# SCH_SIM.net
KiCad netlist of a schematic drawn in Altium Designer
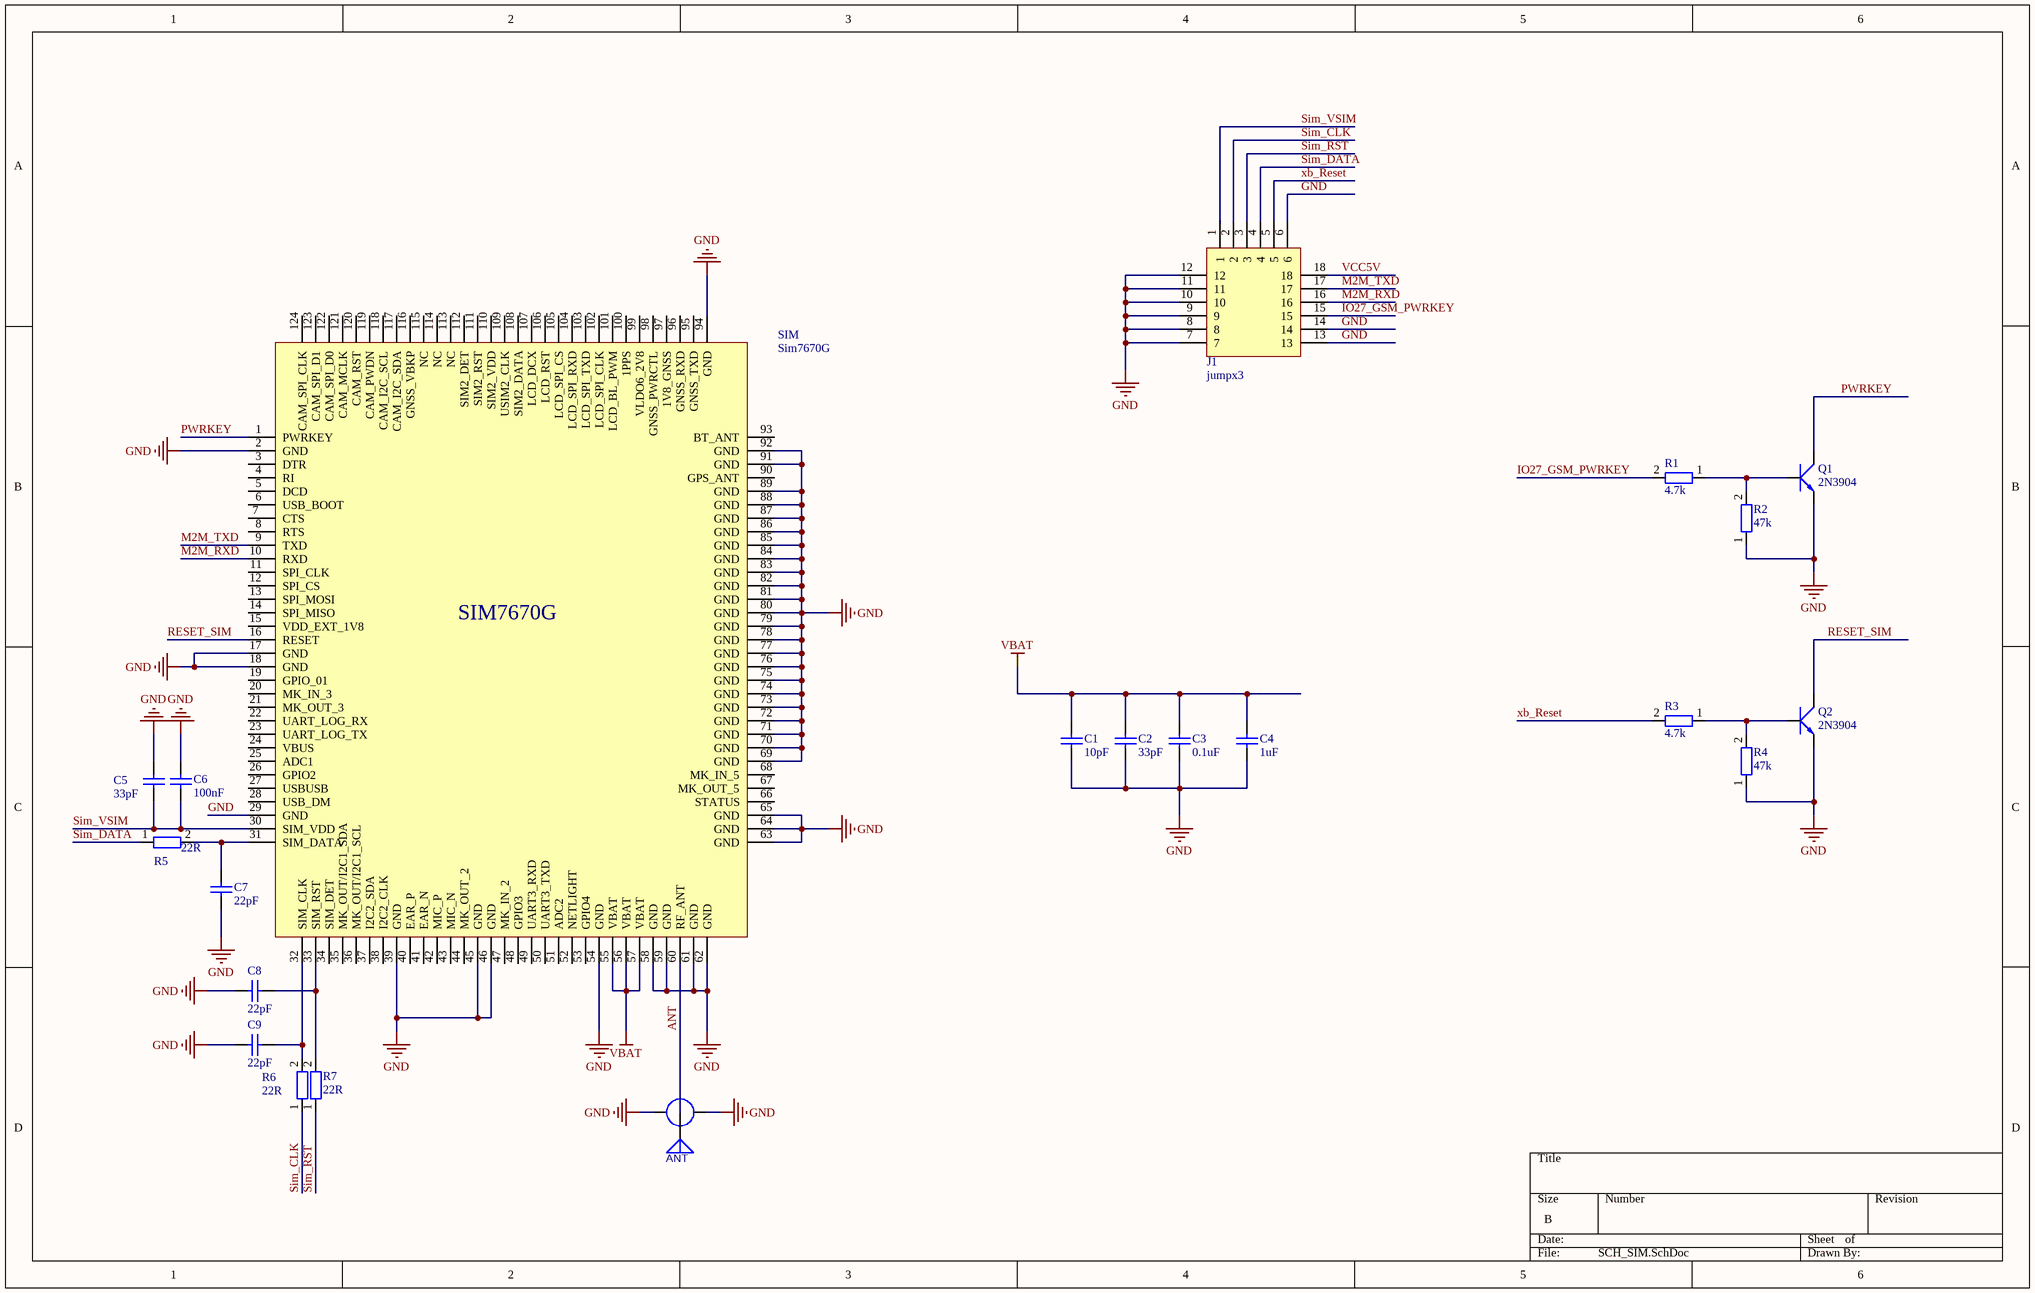
[diagram p0: SCH_SIM.SchDoc]

(export (version "E")
  (design (tool "Eeschema 10.0.6"))
  (components
    (comp (ref "ANT")
      (value "ANT")
      (footprint "CONNECTORS RF SMD TYPE IPEX")
      (description "SMD RF Connectors / Coaxial Connectors ROHS")
      (fields
        (field (name "BOM_SUPPLIER PART") "C3151745")
        (field (name "BOM_MANUFACTURER PART") "IPEX1-TXZ 142")
        (field (name "CONTRIBUTOR") "lcsc")
      )
      (libsource (lib "SCH_Library") (part "CONNECTORS RF SMD"))
    )
    (comp (ref "C1")
      (value "10pF")
      (footprint "C0201")
      (description "Capacitor")
      (libsource (lib "SCH_Library") (part "CAP104-100nF-50V"))
    )
    (comp (ref "C2")
      (value "33pF")
      (footprint "C0201")
      (description "Capacitor")
      (libsource (lib "SCH_Library") (part "CAP104-100nF-50V"))
    )
    (comp (ref "C3")
      (value "0.1uF")
      (footprint "C0201")
      (description "Capacitor")
      (libsource (lib "SCH_Library") (part "CAP104-100nF-50V"))
    )
    (comp (ref "C4")
      (value "1uF")
      (footprint "C0201")
      (description "Capacitor")
      (libsource (lib "SCH_Library") (part "CAP104-100nF-50V"))
    )
    (comp (ref "C5")
      (value "33pF")
      (footprint "C0201")
      (description "Capacitor")
      (libsource (lib "SCH_Library") (part "CAP104-100nF-50V"))
    )
    (comp (ref "C6")
      (value "100nF")
      (footprint "C0201")
      (description "Capacitor")
      (libsource (lib "SCH_Library") (part "CAP104-100nF-50V"))
    )
    (comp (ref "C7")
      (value "22pF")
      (footprint "CAP_0805")
      (description "Capacitor")
      (libsource (lib "SCH_Library") (part "CAP104-100nF-50V"))
    )
    (comp (ref "C8")
      (value "22pF")
      (footprint "C0201")
      (description "Capacitor")
      (libsource (lib "SCH_Library") (part "CAP104-100nF-50V"))
    )
    (comp (ref "C9")
      (value "22pF")
      (footprint "C0201")
      (description "Capacitor")
      (libsource (lib "SCH_Library") (part "CAP104-100nF-50V"))
    )
    (comp (ref "J1") (value "jumpx3") (libsource (lib "SCH_Library") (part "jumpx3")))
    (comp (ref "Q1")
      (value "2N3904")
      (footprint "SOT-23")
      (description "SOT-23 - C8658")
      (libsource (lib "Altium_Lib") (part "Trans BC817"))
    )
    (comp (ref "Q2")
      (value "2N3904")
      (footprint "SOT-23")
      (description "SOT-23 - C8658")
      (libsource (lib "Altium_Lib") (part "Trans BC817"))
    )
    (comp (ref "R1")
      (value "4.7k")
      (footprint "R0201")
      (description "±1% - Chip Resistor - Surface Mount ROHS")
      (libsource (lib "SCH_Library") (part "RES 0603 1%_"))
    )
    (comp (ref "R2")
      (value "47k")
      (footprint "R0201")
      (description "±1% - Chip Resistor - Surface Mount ROHS")
      (libsource (lib "SCH_Library") (part "RES 0603 1%_"))
    )
    (comp (ref "R3")
      (value "4.7k")
      (footprint "R0201")
      (description "±1% - Chip Resistor - Surface Mount ROHS")
      (libsource (lib "SCH_Library") (part "RES 0603 1%_"))
    )
    (comp (ref "R4")
      (value "47k")
      (footprint "R0201")
      (description "±1% - Chip Resistor - Surface Mount ROHS")
      (libsource (lib "SCH_Library") (part "RES 0603 1%_"))
    )
    (comp (ref "R5")
      (value "22R")
      (footprint "R0201")
      (description "±1% - Chip Resistor - Surface Mount ROHS")
      (libsource (lib "SCH_Library") (part "RES 0603 1%_"))
    )
    (comp (ref "R6")
      (value "22R")
      (footprint "R0201")
      (description "±1% - Chip Resistor - Surface Mount ROHS")
      (libsource (lib "SCH_Library") (part "RES 0603 1%_"))
    )
    (comp (ref "R7")
      (value "22R")
      (footprint "R0201")
      (description "±1% - Chip Resistor - Surface Mount ROHS")
      (libsource (lib "SCH_Library") (part "RES 0603 1%_"))
    )
    (comp (ref "SIM")
      (value "Sim7670G")
      (footprint "PCBComponent_1")
      (libsource (lib "SCH_Library") (part "Sim7670G"))
    )
  )
  (nets
    (net (code "1") (name "/ANT") (class "Default")
      (node (ref "ANT") (pin "1") (pinfunction "1_1") (pintype "passive"))
      (node (ref "SIM") (pin "60") (pinfunction "RF_ANT_60") (pintype "passive"))
    )
    (net (code "2") (name "/IO27_GSM_PWRKEY") (class "Default")
      (node (ref "J1") (pin "15") (pinfunction "15_15") (pintype "passive"))
      (node (ref "R1") (pin "2") (pinfunction "2_2") (pintype "passive"))
    )
    (net (code "3") (name "/M2M_RXD") (class "Default")
      (node (ref "J1") (pin "16") (pinfunction "16_16") (pintype "passive"))
      (node (ref "SIM") (pin "10") (pinfunction "RXD_10") (pintype "passive"))
    )
    (net (code "4") (name "/M2M_TXD") (class "Default")
      (node (ref "J1") (pin "17") (pinfunction "17_17") (pintype "passive"))
      (node (ref "SIM") (pin "9") (pinfunction "TXD_9") (pintype "passive"))
    )
    (net (code "5") (name "/PWRKEY") (class "Default")
      (node (ref "Q1") (pin "3") (pinfunction "C_3") (pintype "passive"))
      (node (ref "SIM") (pin "1") (pinfunction "PWRKEY_1") (pintype "passive"))
    )
    (net (code "6") (name "/RESET_SIM") (class "Default")
      (node (ref "Q2") (pin "3") (pinfunction "C_3") (pintype "passive"))
      (node (ref "SIM") (pin "16") (pinfunction "RESET_16") (pintype "passive"))
    )
    (net (code "7") (name "/Sim_CLK") (class "Default")
      (node (ref "J1") (pin "2") (pinfunction "2_2") (pintype "passive"))
      (node (ref "R6") (pin "1") (pinfunction "1_1") (pintype "passive"))
    )
    (net (code "8") (name "/Sim_DATA") (class "Default")
      (node (ref "J1") (pin "4") (pinfunction "4_4") (pintype "passive"))
      (node (ref "R5") (pin "1") (pinfunction "1_1") (pintype "passive"))
    )
    (net (code "9") (name "/Sim_RST") (class "Default")
      (node (ref "J1") (pin "3") (pinfunction "3_3") (pintype "passive"))
      (node (ref "R7") (pin "1") (pinfunction "1_1") (pintype "passive"))
    )
    (net (code "10") (name "/Sim_VSIM") (class "Default")
      (node (ref "C5") (pin "2") (pinfunction "2_2") (pintype "passive"))
      (node (ref "C6") (pin "2") (pinfunction "2_2") (pintype "passive"))
      (node (ref "J1") (pin "1") (pinfunction "1_1") (pintype "passive"))
      (node (ref "SIM") (pin "30") (pinfunction "SIM_VDD_30") (pintype "passive"))
    )
    (net (code "11") (name "/VCC5V") (class "Default")
      (node (ref "J1") (pin "18") (pinfunction "18_18") (pintype "passive"))
    )
    (net (code "12") (name "/xb_Reset") (class "Default")
      (node (ref "J1") (pin "5") (pinfunction "5_5") (pintype "passive"))
      (node (ref "R3") (pin "2") (pinfunction "2_2") (pintype "passive"))
    )
    (net (code "13") (name "GND") (class "Default")
      (node (ref "ANT") (pin "2") (pinfunction "2_2") (pintype "passive"))
      (node (ref "ANT") (pin "3") (pinfunction "3_3") (pintype "passive"))
      (node (ref "C1") (pin "1") (pinfunction "1_1") (pintype "passive"))
      (node (ref "C2") (pin "1") (pinfunction "1_1") (pintype "passive"))
      (node (ref "C3") (pin "1") (pinfunction "1_1") (pintype "passive"))
      (node (ref "C4") (pin "1") (pinfunction "1_1") (pintype "passive"))
      (node (ref "C5") (pin "1") (pinfunction "1_1") (pintype "passive"))
      (node (ref "C6") (pin "1") (pinfunction "1_1") (pintype "passive"))
      (node (ref "C7") (pin "2") (pinfunction "2_2") (pintype "passive"))
      (node (ref "C8") (pin "2") (pinfunction "2_2") (pintype "passive"))
      (node (ref "C9") (pin "2") (pinfunction "2_2") (pintype "passive"))
      (node (ref "J1") (pin "10") (pinfunction "10_10") (pintype "passive"))
      (node (ref "J1") (pin "11") (pinfunction "11_11") (pintype "passive"))
      (node (ref "J1") (pin "12") (pinfunction "12_12") (pintype "passive"))
      (node (ref "J1") (pin "13") (pinfunction "13_13") (pintype "passive"))
      (node (ref "J1") (pin "14") (pinfunction "14_14") (pintype "passive"))
      (node (ref "J1") (pin "6") (pinfunction "6_6") (pintype "passive"))
      (node (ref "J1") (pin "7") (pinfunction "7_7") (pintype "passive"))
      (node (ref "J1") (pin "8") (pinfunction "8_8") (pintype "passive"))
      (node (ref "J1") (pin "9") (pinfunction "9_9") (pintype "passive"))
      (node (ref "Q1") (pin "2") (pinfunction "E_2") (pintype "passive"))
      (node (ref "Q2") (pin "2") (pinfunction "E_2") (pintype "passive"))
      (node (ref "R2") (pin "1") (pinfunction "1_1") (pintype "passive"))
      (node (ref "R4") (pin "1") (pinfunction "1_1") (pintype "passive"))
      (node (ref "SIM") (pin "17") (pinfunction "GND_17") (pintype "passive"))
      (node (ref "SIM") (pin "18") (pinfunction "GND_18") (pintype "passive"))
      (node (ref "SIM") (pin "2") (pinfunction "GND_2") (pintype "passive"))
      (node (ref "SIM") (pin "29") (pinfunction "GND_29") (pintype "passive"))
      (node (ref "SIM") (pin "39") (pinfunction "GND_39") (pintype "passive"))
      (node (ref "SIM") (pin "45") (pinfunction "GND_45") (pintype "passive"))
      (node (ref "SIM") (pin "46") (pinfunction "GND_46") (pintype "passive"))
      (node (ref "SIM") (pin "54") (pinfunction "GND_54") (pintype "passive"))
      (node (ref "SIM") (pin "58") (pinfunction "GND_58") (pintype "passive"))
      (node (ref "SIM") (pin "59") (pinfunction "GND_59") (pintype "passive"))
      (node (ref "SIM") (pin "61") (pinfunction "GND_61") (pintype "passive"))
      (node (ref "SIM") (pin "62") (pinfunction "GND_62") (pintype "passive"))
      (node (ref "SIM") (pin "63") (pinfunction "GND_63") (pintype "passive"))
      (node (ref "SIM") (pin "64") (pinfunction "GND_64") (pintype "passive"))
      (node (ref "SIM") (pin "65") (pinfunction "GND_65") (pintype "passive"))
      (node (ref "SIM") (pin "69") (pinfunction "GND_69") (pintype "passive"))
      (node (ref "SIM") (pin "70") (pinfunction "GND_70") (pintype "passive"))
      (node (ref "SIM") (pin "71") (pinfunction "GND_71") (pintype "passive"))
      (node (ref "SIM") (pin "72") (pinfunction "GND_72") (pintype "passive"))
      (node (ref "SIM") (pin "73") (pinfunction "GND_73") (pintype "passive"))
      (node (ref "SIM") (pin "74") (pinfunction "GND_74") (pintype "passive"))
      (node (ref "SIM") (pin "75") (pinfunction "GND_75") (pintype "passive"))
      (node (ref "SIM") (pin "76") (pinfunction "GND_76") (pintype "passive"))
      (node (ref "SIM") (pin "77") (pinfunction "GND_77") (pintype "passive"))
      (node (ref "SIM") (pin "78") (pinfunction "GND_78") (pintype "passive"))
      (node (ref "SIM") (pin "79") (pinfunction "GND_79") (pintype "passive"))
      (node (ref "SIM") (pin "80") (pinfunction "GND_80") (pintype "passive"))
      (node (ref "SIM") (pin "81") (pinfunction "GND_81") (pintype "passive"))
      (node (ref "SIM") (pin "82") (pinfunction "GND_82") (pintype "passive"))
      (node (ref "SIM") (pin "83") (pinfunction "GND_83") (pintype "passive"))
      (node (ref "SIM") (pin "84") (pinfunction "GND_84") (pintype "passive"))
      (node (ref "SIM") (pin "85") (pinfunction "GND_85") (pintype "passive"))
      (node (ref "SIM") (pin "86") (pinfunction "GND_86") (pintype "passive"))
      (node (ref "SIM") (pin "87") (pinfunction "GND_87") (pintype "passive"))
      (node (ref "SIM") (pin "88") (pinfunction "GND_88") (pintype "passive"))
      (node (ref "SIM") (pin "89") (pinfunction "GND_89") (pintype "passive"))
      (node (ref "SIM") (pin "91") (pinfunction "GND_91") (pintype "passive"))
      (node (ref "SIM") (pin "92") (pinfunction "GND_92") (pintype "passive"))
      (node (ref "SIM") (pin "94") (pinfunction "GND_94") (pintype "passive"))
    )
    (net (code "14") (name "Net-(Q1-B)") (class "Default")
      (node (ref "Q1") (pin "1") (pinfunction "B_1") (pintype "passive"))
      (node (ref "R1") (pin "1") (pinfunction "1_1") (pintype "passive"))
      (node (ref "R2") (pin "2") (pinfunction "2_2") (pintype "passive"))
    )
    (net (code "15") (name "Net-(Q2-B)") (class "Default")
      (node (ref "Q2") (pin "1") (pinfunction "B_1") (pintype "passive"))
      (node (ref "R3") (pin "1") (pinfunction "1_1") (pintype "passive"))
      (node (ref "R4") (pin "2") (pinfunction "2_2") (pintype "passive"))
    )
    (net (code "16") (name "Net-(SIM-SIM_CLK)") (class "Default")
      (node (ref "C9") (pin "1") (pinfunction "1_1") (pintype "passive"))
      (node (ref "R6") (pin "2") (pinfunction "2_2") (pintype "passive"))
      (node (ref "SIM") (pin "32") (pinfunction "SIM_CLK_32") (pintype "passive"))
    )
    (net (code "17") (name "Net-(SIM-SIM_DATA)") (class "Default")
      (node (ref "C7") (pin "1") (pinfunction "1_1") (pintype "passive"))
      (node (ref "R5") (pin "2") (pinfunction "2_2") (pintype "passive"))
      (node (ref "SIM") (pin "31") (pinfunction "SIM_DATA_31") (pintype "passive"))
    )
    (net (code "18") (name "Net-(SIM-SIM_RST)") (class "Default")
      (node (ref "C8") (pin "1") (pinfunction "1_1") (pintype "passive"))
      (node (ref "R7") (pin "2") (pinfunction "2_2") (pintype "passive"))
      (node (ref "SIM") (pin "33") (pinfunction "SIM_RST_33") (pintype "passive"))
    )
    (net (code "19") (name "VBAT") (class "Default")
      (node (ref "C1") (pin "2") (pinfunction "2_2") (pintype "passive"))
      (node (ref "C2") (pin "2") (pinfunction "2_2") (pintype "passive"))
      (node (ref "C3") (pin "2") (pinfunction "2_2") (pintype "passive"))
      (node (ref "C4") (pin "2") (pinfunction "2_2") (pintype "passive"))
      (node (ref "SIM") (pin "55") (pinfunction "VBAT_55") (pintype "passive"))
      (node (ref "SIM") (pin "56") (pinfunction "VBAT_56") (pintype "passive"))
      (node (ref "SIM") (pin "57") (pinfunction "VBAT_57") (pintype "passive"))
    )
    (net (code "20") (name "unconnected-(SIM-1PPS-Pad100)") (class "Default")
      (node (ref "SIM") (pin "100") (pinfunction "1PPS_100") (pintype "passive"))
    )
    (net (code "21") (name "unconnected-(SIM-1V8_GNSS-Pad97)") (class "Default")
      (node (ref "SIM") (pin "97") (pinfunction "1V8_GNSS_97") (pintype "passive"))
    )
    (net (code "22") (name "unconnected-(SIM-ADC1-Pad25)") (class "Default")
      (node (ref "SIM") (pin "25") (pinfunction "ADC1_25") (pintype "passive"))
    )
    (net (code "23") (name "unconnected-(SIM-ADC2-Pad51)") (class "Default")
      (node (ref "SIM") (pin "51") (pinfunction "ADC2_51") (pintype "passive"))
    )
    (net (code "24") (name "unconnected-(SIM-BT_ANT-Pad93)") (class "Default")
      (node (ref "SIM") (pin "93") (pinfunction "BT_ANT_93") (pintype "passive"))
    )
    (net (code "25") (name "unconnected-(SIM-CAM_I2C_SCL-Pad118)") (class "Default")
      (node (ref "SIM") (pin "118") (pinfunction "CAM_I2C_SCL_118") (pintype "passive"))
    )
    (net (code "26") (name "unconnected-(SIM-CAM_I2C_SDA-Pad117)") (class "Default")
      (node (ref "SIM") (pin "117") (pinfunction "CAM_I2C_SDA_117") (pintype "passive"))
    )
    (net (code "27") (name "unconnected-(SIM-CAM_MCLK-Pad121)") (class "Default")
      (node (ref "SIM") (pin "121") (pinfunction "CAM_MCLK_121") (pintype "passive"))
    )
    (net (code "28") (name "unconnected-(SIM-CAM_PWDN-Pad119)") (class "Default")
      (node (ref "SIM") (pin "119") (pinfunction "CAM_PWDN_119") (pintype "passive"))
    )
    (net (code "29") (name "unconnected-(SIM-CAM_RST-Pad120)") (class "Default")
      (node (ref "SIM") (pin "120") (pinfunction "CAM_RST_120") (pintype "passive"))
    )
    (net (code "30") (name "unconnected-(SIM-CAM_SPI_CLK-Pad124)") (class "Default")
      (node (ref "SIM") (pin "124") (pinfunction "CAM_SPI_CLK_124") (pintype "passive"))
    )
    (net (code "31") (name "unconnected-(SIM-CAM_SPI_D0-Pad122)") (class "Default")
      (node (ref "SIM") (pin "122") (pinfunction "CAM_SPI_D0_122") (pintype "passive"))
    )
    (net (code "32") (name "unconnected-(SIM-CAM_SPI_D1-Pad123)") (class "Default")
      (node (ref "SIM") (pin "123") (pinfunction "CAM_SPI_D1_123") (pintype "passive"))
    )
    (net (code "33") (name "unconnected-(SIM-CTS-Pad7)") (class "Default")
      (node (ref "SIM") (pin "7") (pinfunction "CTS_7") (pintype "passive"))
    )
    (net (code "34") (name "unconnected-(SIM-DCD-Pad5)") (class "Default")
      (node (ref "SIM") (pin "5") (pinfunction "DCD_5") (pintype "passive"))
    )
    (net (code "35") (name "unconnected-(SIM-DTR-Pad3)") (class "Default")
      (node (ref "SIM") (pin "3") (pinfunction "DTR_3") (pintype "passive"))
    )
    (net (code "36") (name "unconnected-(SIM-EAR_N-Pad41)") (class "Default")
      (node (ref "SIM") (pin "41") (pinfunction "EAR_N_41") (pintype "passive"))
    )
    (net (code "37") (name "unconnected-(SIM-EAR_P-Pad40)") (class "Default")
      (node (ref "SIM") (pin "40") (pinfunction "EAR_P_40") (pintype "passive"))
    )
    (net (code "38") (name "unconnected-(SIM-GNSS_PWRCTL-Pad98)") (class "Default")
      (node (ref "SIM") (pin "98") (pinfunction "GNSS_PWRCTL_98") (pintype "passive"))
    )
    (net (code "39") (name "unconnected-(SIM-GNSS_RXD-Pad96)") (class "Default")
      (node (ref "SIM") (pin "96") (pinfunction "GNSS_RXD_96") (pintype "passive"))
    )
    (net (code "40") (name "unconnected-(SIM-GNSS_TXD-Pad95)") (class "Default")
      (node (ref "SIM") (pin "95") (pinfunction "GNSS_TXD_95") (pintype "passive"))
    )
    (net (code "41") (name "unconnected-(SIM-GNSS_VBKP-Pad116)") (class "Default")
      (node (ref "SIM") (pin "116") (pinfunction "GNSS_VBKP_116") (pintype "passive"))
    )
    (net (code "42") (name "unconnected-(SIM-GPIO2-Pad26)") (class "Default")
      (node (ref "SIM") (pin "26") (pinfunction "GPIO2_26") (pintype "passive"))
    )
    (net (code "43") (name "unconnected-(SIM-GPIO3-Pad48)") (class "Default")
      (node (ref "SIM") (pin "48") (pinfunction "GPIO3_48") (pintype "passive"))
    )
    (net (code "44") (name "unconnected-(SIM-GPIO4-Pad53)") (class "Default")
      (node (ref "SIM") (pin "53") (pinfunction "GPIO4_53") (pintype "passive"))
    )
    (net (code "45") (name "unconnected-(SIM-GPIO_01-Pad19)") (class "Default")
      (node (ref "SIM") (pin "19") (pinfunction "GPIO_01_19") (pintype "passive"))
    )
    (net (code "46") (name "unconnected-(SIM-GPS_ANT-Pad90)") (class "Default")
      (node (ref "SIM") (pin "90") (pinfunction "GPS_ANT_90") (pintype "passive"))
    )
    (net (code "47") (name "unconnected-(SIM-I2C2_CLK-Pad38)") (class "Default")
      (node (ref "SIM") (pin "38") (pinfunction "I2C2_CLK_38") (pintype "passive"))
    )
    (net (code "48") (name "unconnected-(SIM-I2C2_SDA-Pad37)") (class "Default")
      (node (ref "SIM") (pin "37") (pinfunction "I2C2_SDA_37") (pintype "passive"))
    )
    (net (code "49") (name "unconnected-(SIM-LCD_BL_PWM-Pad101)") (class "Default")
      (node (ref "SIM") (pin "101") (pinfunction "LCD_BL_PWM_101") (pintype "passive"))
    )
    (net (code "50") (name "unconnected-(SIM-LCD_DCX-Pad107)") (class "Default")
      (node (ref "SIM") (pin "107") (pinfunction "LCD_DCX_107") (pintype "passive"))
    )
    (net (code "51") (name "unconnected-(SIM-LCD_RST-Pad106)") (class "Default")
      (node (ref "SIM") (pin "106") (pinfunction "LCD_RST_106") (pintype "passive"))
    )
    (net (code "52") (name "unconnected-(SIM-LCD_SPI_CLK-Pad102)") (class "Default")
      (node (ref "SIM") (pin "102") (pinfunction "LCD_SPI_CLK_102") (pintype "passive"))
    )
    (net (code "53") (name "unconnected-(SIM-LCD_SPI_CS-Pad105)") (class "Default")
      (node (ref "SIM") (pin "105") (pinfunction "LCD_SPI_CS_105") (pintype "passive"))
    )
    (net (code "54") (name "unconnected-(SIM-LCD_SPI_RXD-Pad104)") (class "Default")
      (node (ref "SIM") (pin "104") (pinfunction "LCD_SPI_RXD_104") (pintype "passive"))
    )
    (net (code "55") (name "unconnected-(SIM-LCD_SPI_TXD-Pad103)") (class "Default")
      (node (ref "SIM") (pin "103") (pinfunction "LCD_SPI_TXD_103") (pintype "passive"))
    )
    (net (code "56") (name "unconnected-(SIM-MIC_N-Pad43)") (class "Default")
      (node (ref "SIM") (pin "43") (pinfunction "MIC_N_43") (pintype "passive"))
    )
    (net (code "57") (name "unconnected-(SIM-MIC_P-Pad42)") (class "Default")
      (node (ref "SIM") (pin "42") (pinfunction "MIC_P_42") (pintype "passive"))
    )
    (net (code "58") (name "unconnected-(SIM-MK_IN_2-Pad47)") (class "Default")
      (node (ref "SIM") (pin "47") (pinfunction "MK_IN_2_47") (pintype "passive"))
    )
    (net (code "59") (name "unconnected-(SIM-MK_IN_3-Pad20)") (class "Default")
      (node (ref "SIM") (pin "20") (pinfunction "MK_IN_3_20") (pintype "passive"))
    )
    (net (code "60") (name "unconnected-(SIM-MK_IN_5-Pad68)") (class "Default")
      (node (ref "SIM") (pin "68") (pinfunction "MK_IN_5_68") (pintype "passive"))
    )
    (net (code "61") (name "unconnected-(SIM-MK_OUT_2-Pad44)") (class "Default")
      (node (ref "SIM") (pin "44") (pinfunction "MK_OUT_2_44") (pintype "passive"))
    )
    (net (code "62") (name "unconnected-(SIM-MK_OUT_3-Pad21)") (class "Default")
      (node (ref "SIM") (pin "21") (pinfunction "MK_OUT_3_21") (pintype "passive"))
    )
    (net (code "63") (name "unconnected-(SIM-MK_OUT_5-Pad67)") (class "Default")
      (node (ref "SIM") (pin "67") (pinfunction "MK_OUT_5_67") (pintype "passive"))
    )
    (net (code "64") (name "unconnected-(SIM-MK_OUT{slash}I2C1_SCL-Pad36)") (class "Default")
      (node (ref "SIM") (pin "36") (pinfunction "MK_OUT/I2C1_SCL_36") (pintype "passive"))
    )
    (net (code "65") (name "unconnected-(SIM-MK_OUT{slash}I2C1_SDA-Pad35)") (class "Default")
      (node (ref "SIM") (pin "35") (pinfunction "MK_OUT/I2C1_SDA_35") (pintype "passive"))
    )
    (net (code "66") (name "unconnected-(SIM-NC-Pad113)") (class "Default")
      (node (ref "SIM") (pin "113") (pinfunction "NC_113") (pintype "passive"))
    )
    (net (code "67") (name "unconnected-(SIM-NC-Pad114)") (class "Default")
      (node (ref "SIM") (pin "114") (pinfunction "NC_114") (pintype "passive"))
    )
    (net (code "68") (name "unconnected-(SIM-NC-Pad115)") (class "Default")
      (node (ref "SIM") (pin "115") (pinfunction "NC_115") (pintype "passive"))
    )
    (net (code "69") (name "unconnected-(SIM-NETLIGHT-Pad52)") (class "Default")
      (node (ref "SIM") (pin "52") (pinfunction "NETLIGHT_52") (pintype "passive"))
    )
    (net (code "70") (name "unconnected-(SIM-RI-Pad4)") (class "Default")
      (node (ref "SIM") (pin "4") (pinfunction "RI_4") (pintype "passive"))
    )
    (net (code "71") (name "unconnected-(SIM-RTS-Pad8)") (class "Default")
      (node (ref "SIM") (pin "8") (pinfunction "RTS_8") (pintype "passive"))
    )
    (net (code "72") (name "unconnected-(SIM-SIM2_DATA-Pad108)") (class "Default")
      (node (ref "SIM") (pin "108") (pinfunction "SIM2_DATA_108") (pintype "passive"))
    )
    (net (code "73") (name "unconnected-(SIM-SIM2_DET-Pad112)") (class "Default")
      (node (ref "SIM") (pin "112") (pinfunction "SIM2_DET_112") (pintype "passive"))
    )
    (net (code "74") (name "unconnected-(SIM-SIM2_RST-Pad111)") (class "Default")
      (node (ref "SIM") (pin "111") (pinfunction "SIM2_RST_111") (pintype "passive"))
    )
    (net (code "75") (name "unconnected-(SIM-SIM2_VDD-Pad110)") (class "Default")
      (node (ref "SIM") (pin "110") (pinfunction "SIM2_VDD_110") (pintype "passive"))
    )
    (net (code "76") (name "unconnected-(SIM-SIM_DET-Pad34)") (class "Default")
      (node (ref "SIM") (pin "34") (pinfunction "SIM_DET_34") (pintype "passive"))
    )
    (net (code "77") (name "unconnected-(SIM-SPI_CLK-Pad11)") (class "Default")
      (node (ref "SIM") (pin "11") (pinfunction "SPI_CLK_11") (pintype "passive"))
    )
    (net (code "78") (name "unconnected-(SIM-SPI_CS-Pad12)") (class "Default")
      (node (ref "SIM") (pin "12") (pinfunction "SPI_CS_12") (pintype "passive"))
    )
    (net (code "79") (name "unconnected-(SIM-SPI_MISO-Pad14)") (class "Default")
      (node (ref "SIM") (pin "14") (pinfunction "SPI_MISO_14") (pintype "passive"))
    )
    (net (code "80") (name "unconnected-(SIM-SPI_MOSI-Pad13)") (class "Default")
      (node (ref "SIM") (pin "13") (pinfunction "SPI_MOSI_13") (pintype "passive"))
    )
    (net (code "81") (name "unconnected-(SIM-STATUS-Pad66)") (class "Default")
      (node (ref "SIM") (pin "66") (pinfunction "STATUS_66") (pintype "passive"))
    )
    (net (code "82") (name "unconnected-(SIM-UART3_RXD-Pad49)") (class "Default")
      (node (ref "SIM") (pin "49") (pinfunction "UART3_RXD_49") (pintype "passive"))
    )
    (net (code "83") (name "unconnected-(SIM-UART3_TXD-Pad50)") (class "Default")
      (node (ref "SIM") (pin "50") (pinfunction "UART3_TXD_50") (pintype "passive"))
    )
    (net (code "84") (name "unconnected-(SIM-UART_LOG_RX-Pad22)") (class "Default")
      (node (ref "SIM") (pin "22") (pinfunction "UART_LOG_RX_22") (pintype "passive"))
    )
    (net (code "85") (name "unconnected-(SIM-UART_LOG_TX-Pad23)") (class "Default")
      (node (ref "SIM") (pin "23") (pinfunction "UART_LOG_TX_23") (pintype "passive"))
    )
    (net (code "86") (name "unconnected-(SIM-USBUSB-Pad27)") (class "Default")
      (node (ref "SIM") (pin "27") (pinfunction "USBUSB_27") (pintype "passive"))
    )
    (net (code "87") (name "unconnected-(SIM-USB_BOOT-Pad6)") (class "Default")
      (node (ref "SIM") (pin "6") (pinfunction "USB_BOOT_6") (pintype "passive"))
    )
    (net (code "88") (name "unconnected-(SIM-USB_DM-Pad28)") (class "Default")
      (node (ref "SIM") (pin "28") (pinfunction "USB_DM_28") (pintype "passive"))
    )
    (net (code "89") (name "unconnected-(SIM-USIM2_CLK-Pad109)") (class "Default")
      (node (ref "SIM") (pin "109") (pinfunction "USIM2_CLK_109") (pintype "passive"))
    )
    (net (code "90") (name "unconnected-(SIM-VBUS-Pad24)") (class "Default")
      (node (ref "SIM") (pin "24") (pinfunction "VBUS_24") (pintype "passive"))
    )
    (net (code "91") (name "unconnected-(SIM-VDD_EXT_1V8-Pad15)") (class "Default")
      (node (ref "SIM") (pin "15") (pinfunction "VDD_EXT_1V8_15") (pintype "passive"))
    )
    (net (code "92") (name "unconnected-(SIM-VLDO6_2V8-Pad99)") (class "Default")
      (node (ref "SIM") (pin "99") (pinfunction "VLDO6_2V8_99") (pintype "passive"))
    )
  )
)
